# Base_Station_Schematic.net
KiCad netlist of a schematic drawn in Altium Designer
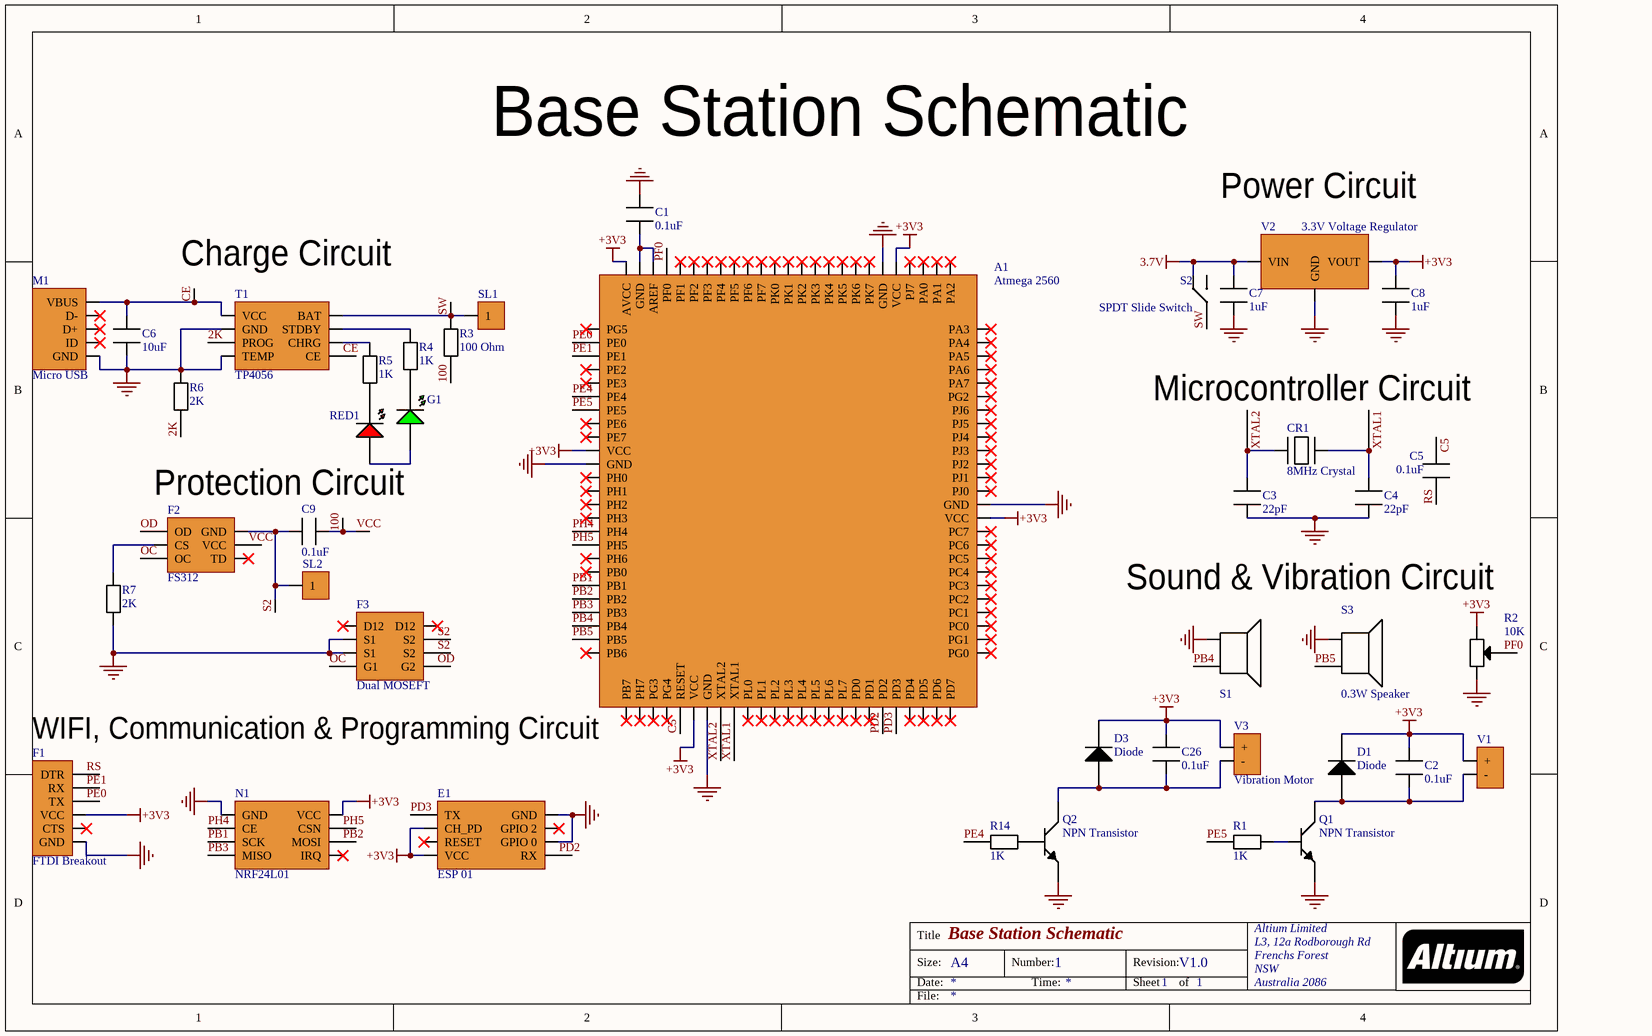
[diagram p0: Base Station Schematic.SchDoc]

(export (version "E")
  (design (tool "Eeschema 10.0.6"))
  (components
    (comp (ref "A1")
      (value "Atmega 2560")
      (footprint "Atmega 2560")
      (fields
        (field (name "MANUFACTURER") "Microchip / Atmel")
        (field (name "MANUFACTURER PART NUMBER") "ATMEGA2560V-8AU")
      )
      (libsource (lib "Schematic Library") (part "ATMEGA2560V-8AU"))
    )
    (comp (ref "C1")
      (value "0.1uF")
      (footprint "0.1uF Capacitor")
      (description "CAP CER 0.1UF 25V X7R 0603")
      (fields
        (field (name "MANUFACTURER") "Kyocera AVX")
        (field (name "MANUFACTURER PART NUMBER") "06033C104KAT4A")
      )
      (libsource (lib "Schematic Library") (part "06033C104KAT4A"))
    )
    (comp (ref "C2")
      (value "0.1uF")
      (footprint "0.1uF Capacitor")
      (description "CAP CER 0.1UF 25V X7R 0603")
      (fields
        (field (name "MANUFACTURER") "Kyocera AVX")
        (field (name "MANUFACTURER PART NUMBER") "06033C104KAT4A")
      )
      (libsource (lib "Schematic Library") (part "06033C104KAT4A"))
    )
    (comp (ref "C3")
      (value "22pF")
      (footprint "22pF Capacitor")
      (description "Cap Ceramic 22pF 50V C0G 5% SMD 0603 125C Paper T/R")
      (fields
        (field (name "MANUFACTURER") "Kyocera AVX")
        (field (name "MANUFACTURER PART NUMBER") "06035A220JAT2A")
      )
      (libsource (lib "Schematic Library") (part "06035A220JAT2A"))
    )
    (comp (ref "C4")
      (value "22pF")
      (footprint "22pF Capacitor")
      (description "Cap Ceramic 22pF 50V C0G 5% SMD 0603 125C Paper T/R")
      (fields
        (field (name "MANUFACTURER") "Kyocera AVX")
        (field (name "MANUFACTURER PART NUMBER") "06035A220JAT2A")
      )
      (libsource (lib "Schematic Library") (part "06035A220JAT2A"))
    )
    (comp (ref "C5")
      (value "0.1uF")
      (footprint "0.1uF Capacitor")
      (description "CAP CER 0.1UF 25V X7R 0603")
      (fields
        (field (name "MANUFACTURER") "Kyocera AVX")
        (field (name "MANUFACTURER PART NUMBER") "06033C104KAT4A")
      )
      (libsource (lib "Schematic Library") (part "06033C104KAT4A"))
    )
    (comp (ref "C6")
      (value "10uF")
      (footprint "10uF Capactior")
      (fields
        (field (name "MANUFACTURER") "Kyocera AVX")
        (field (name "MANUFACTURER PART NUMBER") "06036D106MAT2A")
        (field (name "TOLERANCE") "20%")
      )
      (libsource (lib "Schematic Library") (part "06036D106MAT2A"))
    )
    (comp (ref "C7")
      (value "1uF")
      (footprint "1uF Capacitor")
      (description "Cap Ceramic 1uF 10V X5R 10% Pad SMD 0603 85C T/R")
      (fields
        (field (name "MANUFACTURER") "Kyocera AVX")
        (field (name "MANUFACTURER PART NUMBER") "0603ZD105KAT2A")
      )
      (libsource (lib "Schematic Library") (part "0603ZD105KAT2A"))
    )
    (comp (ref "C8")
      (value "1uF")
      (footprint "1uF Capacitor")
      (description "Cap Ceramic 1uF 10V X5R 10% Pad SMD 0603 85C T/R")
      (fields
        (field (name "MANUFACTURER") "Kyocera AVX")
        (field (name "MANUFACTURER PART NUMBER") "0603ZD105KAT2A")
      )
      (libsource (lib "Schematic Library") (part "0603ZD105KAT2A"))
    )
    (comp (ref "C9")
      (value "0.1uF")
      (footprint "0.1uF Capacitor")
      (description "CAP CER 0.1UF 25V X7R 0603")
      (fields
        (field (name "MANUFACTURER") "Kyocera AVX")
        (field (name "MANUFACTURER PART NUMBER") "06033C104KAT4A")
      )
      (libsource (lib "Schematic Library") (part "06033C104KAT4A"))
    )
    (comp (ref "C26")
      (value "0.1uF")
      (footprint "0.1uF Capacitor")
      (description "CAP CER 0.1UF 25V X7R 0603")
      (fields
        (field (name "MANUFACTURER") "Kyocera AVX")
        (field (name "MANUFACTURER PART NUMBER") "06033C104KAT4A")
      )
      (libsource (lib "Schematic Library") (part "06033C104KAT4A"))
    )
    (comp (ref "CR1")
      (value "8MHz Crystal")
      (footprint "8MHz Crystal")
      (description "Crystal 8MHz ±30ppm (Tol) ±50ppm (Stability) 20pF FUND 80Ohm 2-Pin HC-49/SDLF SMD T/R")
      (fields
        (field (name "MANUFACTURER") "Fox Electronics")
        (field (name "MANUFACTURER PART NUMBER") "FC4SDCBMF8.0-T1")
      )
      (libsource (lib "Schematic Library") (part "FC4SDCBMF8.0-T1"))
    )
    (comp (ref "D1")
      (value "Diode")
      (footprint "Diode")
      (description "BOURNS - CD0603-B0240R - Kleinsignal-Schottky-Diode, Einfach, 40 V, 200 mA, 500 mV, 2 A, 125 °C")
      (fields
        (field (name "MANUFACTURER") "Bourns")
        (field (name "MANUFACTURER PART NUMBER") "CD0603-B0240R")
      )
      (libsource (lib "Schematic Library") (part "CD0603-B0240R"))
    )
    (comp (ref "D3")
      (value "Diode")
      (footprint "Diode")
      (description "BOURNS - CD0603-B0240R - Kleinsignal-Schottky-Diode, Einfach, 40 V, 200 mA, 500 mV, 2 A, 125 °C")
      (fields
        (field (name "MANUFACTURER") "Bourns")
        (field (name "MANUFACTURER PART NUMBER") "CD0603-B0240R")
      )
      (libsource (lib "Schematic Library") (part "CD0603-B0240R"))
    )
    (comp (ref "E1")
      (value "ESP 01")
      (footprint "ESP 01")
      (description "ESP8266 ESP-01 Serial WIFI Wireless Transceiver Module Send Receive LWIP AP+STA")
      (libsource (lib "Schematic Library") (part "ESP 01"))
    )
    (comp (ref "F1")
      (value "FTDI Breakout")
      (footprint "FTDI")
      (description "FTDI USB to TTL serial converter module")
      (libsource (lib "Schematic Library") (part "FTDI"))
    )
    (comp (ref "F2")
      (value "FS312")
      (footprint "FS312")
      (description "ONE CELL LI-ION/LI-PO BATTERY PROTECTION IC")
      (libsource (lib "Schematic Library") (part "FS312"))
    )
    (comp (ref "F3")
      (value "Dual MOSEFT")
      (footprint "FS8205")
      (description "FS8205A DUAL N-CHANNEL POWER MOSFET")
      (libsource (lib "Schematic Library") (part "FS8205"))
    )
    (comp (ref "G1")
      (value "Green LED")
      (footprint "Green LED")
      (description "WURTH ELEKTRONIK - 151051VS04000 - LED, Green, Through Hole, T-1 3/4 (5mm), 30 mA, 2.1 V, 572 nm")
      (fields
        (field (name "MANUFACTURER") "Wurth Electronics")
        (field (name "MANUFACTURER PART NUMBER") "151051VS04000")
      )
      (libsource (lib "Schematic Library") (part "151051VS04000"))
    )
    (comp (ref "M1")
      (value "Micro USB")
      (footprint "Micro USB")
      (fields
        (field (name "MANUFACTURER") "Wurth Electronics")
        (field (name "MANUFACTURER PART NUMBER") "629105136821")
      )
      (libsource (lib "Schematic Library") (part "629105136821"))
    )
    (comp (ref "N1")
      (value "NRF24L01")
      (footprint "NRF24L01")
      (description "3.3V NRF24L01 WIRELESS RF MODULE")
      (libsource (lib "Schematic Library") (part "NRF24L01"))
    )
    (comp (ref "Q1")
      (value "NPN Transistor")
      (footprint "NPN Transistor")
      (description "MMBT3904 Series 40 V 200 mA 250 mW NPN Switching Transistor - SOT-23-3")
      (fields
        (field (name "MANUFACTURER") "Nexperia")
        (field (name "MANUFACTURER PART NUMBER") "MMBT3904,215")
      )
      (libsource (lib "Schematic Library") (part "MMBT3904,215"))
    )
    (comp (ref "Q2")
      (value "NPN Transistor")
      (footprint "NPN Transistor")
      (description "MMBT3904 Series 40 V 200 mA 250 mW NPN Switching Transistor - SOT-23-3")
      (fields
        (field (name "MANUFACTURER") "Nexperia")
        (field (name "MANUFACTURER PART NUMBER") "MMBT3904,215")
      )
      (libsource (lib "Schematic Library") (part "MMBT3904,215"))
    )
    (comp (ref "R1")
      (value "1K")
      (footprint "1K Resistor")
      (description "RES 1K OHM 0.01% 1/10W 0603")
      (fields
        (field (name "MANUFACTURER") "Stackpole Electronics")
        (field (name "MANUFACTURER PART NUMBER") "RNCF0603TKY1K00")
      )
      (libsource (lib "Schematic Library") (part "RNCF0603TKY1K00"))
    )
    (comp (ref "R2")
      (value "10K")
      (footprint "10K Potentiometer")
      (fields
        (field (name "MANUFACTURER") "Bourns")
        (field (name "MANUFACTURER PART NUMBER") "91A1A-B28-B15L")
        (field (name "TOLERANCE") "20%")
      )
      (libsource (lib "Schematic Library") (part "91A1A-B28-B15L"))
    )
    (comp (ref "R3")
      (value "100 Ohm")
      (footprint "100 Ohm Resistor")
      (description "RES SMD 100 OHM 0.01% 1/10W 0603")
      (fields
        (field (name "MANUFACTURER") "Stackpole Electronics")
        (field (name "MANUFACTURER PART NUMBER") "RNCF0603TKY100R")
      )
      (libsource (lib "Schematic Library") (part "RNCF0603TKY100R"))
    )
    (comp (ref "R4")
      (value "1K")
      (footprint "1K Resistor")
      (description "RES 1K OHM 0.01% 1/10W 0603")
      (fields
        (field (name "MANUFACTURER") "Stackpole Electronics")
        (field (name "MANUFACTURER PART NUMBER") "RNCF0603TKY1K00")
      )
      (libsource (lib "Schematic Library") (part "RNCF0603TKY1K00"))
    )
    (comp (ref "R5")
      (value "1K")
      (footprint "1K Resistor")
      (description "RES 1K OHM 0.01% 1/10W 0603")
      (fields
        (field (name "MANUFACTURER") "Stackpole Electronics")
        (field (name "MANUFACTURER PART NUMBER") "RNCF0603TKY1K00")
      )
      (libsource (lib "Schematic Library") (part "RNCF0603TKY1K00"))
    )
    (comp (ref "R6")
      (value "2K")
      (footprint "2K Resistor")
      (description "RES 2K OHM 0.01% 1/10W 0603")
      (fields
        (field (name "MANUFACTURER") "Stackpole Electronics")
        (field (name "MANUFACTURER PART NUMBER") "RNCF0603TKY2K00")
      )
      (libsource (lib "Schematic Library") (part "RNCF0603TKY2K00"))
    )
    (comp (ref "R7")
      (value "2K")
      (footprint "2K Resistor")
      (description "RES 2K OHM 0.01% 1/10W 0603")
      (fields
        (field (name "MANUFACTURER") "Stackpole Electronics")
        (field (name "MANUFACTURER PART NUMBER") "RNCF0603TKY2K00")
      )
      (libsource (lib "Schematic Library") (part "RNCF0603TKY2K00"))
    )
    (comp (ref "R14")
      (value "1K")
      (footprint "1K Resistor")
      (description "RES 1K OHM 0.01% 1/10W 0603")
      (fields
        (field (name "MANUFACTURER") "Stackpole Electronics")
        (field (name "MANUFACTURER PART NUMBER") "RNCF0603TKY1K00")
      )
      (libsource (lib "Schematic Library") (part "RNCF0603TKY1K00"))
    )
    (comp (ref "RED1")
      (value "Red LED")
      (footprint "Red LED")
      (description "WURTH ELEKTRONIK - 151051RS11000 - LED, Red, Through Hole, T-1 3/4 (5mm), 30 mA, 2.1 V, 630 nm")
      (fields
        (field (name "MANUFACTURER") "Wurth Electronics")
        (field (name "MANUFACTURER PART NUMBER") "151051RS11000")
      )
      (libsource (lib "Schematic Library") (part "151051RS11000"))
    )
    (comp (ref "S1")
      (value "0.3W Speaker")
      (footprint "0.3W Speaker")
      (description "SPEAKER, 8OHM, 0.3W, 60MM")
      (fields
        (field (name "MANUFACTURER") "CQR Components")
        (field (name "MANUFACTURER PART NUMBER") "SPEAKERMINIATURE2.5\"8OHM")
      )
      (libsource (lib "Schematic Library") (part "SPEAKERMINIATURE2.5{dblquote}8OHM"))
    )
    (comp (ref "S2")
      (value "SPDT Slide Switch")
      (footprint "Slide Switch")
      (description "Slide Switch, JS Series, SPDT, Right Angle, SMD, 100 mA ;RoHS Compliant: Yes")
      (fields
        (field (name "MANUFACTURER") "ITT C&K")
        (field (name "MANUFACTURER PART NUMBER") "JS102011SAQN")
      )
      (libsource (lib "Schematic Library") (part "JS102011SAQN"))
    )
    (comp (ref "S3")
      (value "0.3W Speaker")
      (footprint "0.3W Speaker")
      (description "SPEAKER, 8OHM, 0.3W, 60MM")
      (fields
        (field (name "MANUFACTURER") "CQR Components")
        (field (name "MANUFACTURER PART NUMBER") "SPEAKERMINIATURE2.5\"8OHM")
      )
      (libsource (lib "Schematic Library") (part "SPEAKERMINIATURE2.5{dblquote}8OHM"))
    )
    (comp (ref "SL1")
      (value "Solder Pads")
      (footprint "Solder Pads")
      (description "CONN HEADER VERT 1POS")
      (fields
        (field (name "MANUFACTURER") "Wurth Electronics")
        (field (name "MANUFACTURER PART NUMBER") "61300111121")
      )
      (libsource (lib "Schematic Library") (part "61300111121"))
    )
    (comp (ref "SL2")
      (value "Solder Pads")
      (footprint "Solder Pads")
      (description "CONN HEADER VERT 1POS")
      (fields
        (field (name "MANUFACTURER") "Wurth Electronics")
        (field (name "MANUFACTURER PART NUMBER") "61300111121")
      )
      (libsource (lib "Schematic Library") (part "61300111121"))
    )
    (comp (ref "T1")
      (value "TP4056")
      (footprint "TP4056")
      (description "TP4056 1A Standalone Linear Li-lon Battery Charger with Thermal\r\nRegulation in SOP-8")
      (libsource (lib "Schematic Library") (part "TP4056"))
    )
    (comp (ref "V1")
      (value "Vibration Motor")
      (footprint "Vibration Motor")
      (description "Vibration Erm Motor 9000 Rpm 3V")
      (fields
        (field (name "MANUFACTURER") "Jinlong Machinery & Electronics")
        (field (name "MANUFACTURER PART NUMBER") "C1030B028F")
      )
      (libsource (lib "") (part "C1030B028F_1"))
    )
    (comp (ref "V2")
      (value "3.3V Voltage Regulator")
      (footprint "Voltage Regulator")
      (description "IC REG LINEAR 3.3V 1A SOT223")
      (fields
        (field (name "MANUFACTURER") "Diodes")
        (field (name "MANUFACTURER PART NUMBER") "AZ1117EH-3.3TRG1")
      )
      (libsource (lib "Schematic Library") (part "AZ1117EH-3.3TRG1"))
    )
    (comp (ref "V3")
      (value "Vibration Motor")
      (footprint "Vibration Motor")
      (description "Vibration Erm Motor 9000 Rpm 3V")
      (fields
        (field (name "MANUFACTURER") "Jinlong Machinery & Electronics")
        (field (name "MANUFACTURER PART NUMBER") "C1030B028F")
      )
      (libsource (lib "Schematic Library") (part "C1030B028F"))
    )
  )
  (nets
    (net (code "1") (name "+3V3") (class "Default")
      (node (ref "A1") (pin "10") (pinfunction "VCC_10") (pintype "passive"))
      (node (ref "A1") (pin "100") (pinfunction "AVCC_100") (pintype "passive"))
      (node (ref "A1") (pin "31") (pinfunction "VCC_31") (pintype "passive"))
      (node (ref "A1") (pin "61") (pinfunction "VCC_61") (pintype "passive"))
      (node (ref "A1") (pin "80") (pinfunction "VCC_80") (pintype "passive"))
      (node (ref "C2") (pin "1") (pinfunction "1_1") (pintype "passive"))
      (node (ref "C26") (pin "2") (pinfunction "2_2") (pintype "passive"))
      (node (ref "C8") (pin "2") (pinfunction "2_2") (pintype "passive"))
      (node (ref "D1") (pin "1") (pinfunction "1_1") (pintype "passive"))
      (node (ref "D3") (pin "1") (pinfunction "1_1") (pintype "passive"))
      (node (ref "E1") (pin "2") (pinfunction "CH_PD_2") (pintype "passive"))
      (node (ref "E1") (pin "4") (pinfunction "VCC_4") (pintype "passive"))
      (node (ref "F1") (pin "4") (pinfunction "VCC_4") (pintype "passive"))
      (node (ref "N1") (pin "5") (pinfunction "VCC_5") (pintype "passive"))
      (node (ref "R2") (pin "1") (pinfunction "1_1") (pintype "passive"))
      (node (ref "V1") (pin "2") (pinfunction "+_2") (pintype "passive"))
      (node (ref "V2") (pin "2") (pinfunction "VOUT_2") (pintype "passive"))
      (node (ref "V3") (pin "2") (pinfunction "+_2") (pintype "passive"))
    )
    (net (code "2") (name "/2K") (class "Default")
      (node (ref "R6") (pin "1") (pinfunction "1_1") (pintype "passive"))
      (node (ref "T1") (pin "2") (pinfunction "PROG_2") (pintype "passive"))
    )
    (net (code "3") (name "/100") (class "Default")
      (node (ref "C9") (pin "1") (pinfunction "1_1") (pintype "passive"))
      (node (ref "F2") (pin "5") (pinfunction "VCC_5") (pintype "passive"))
      (node (ref "R3") (pin "2") (pinfunction "2_2") (pintype "passive"))
    )
    (net (code "4") (name "/C5") (class "Default")
      (node (ref "A1") (pin "30") (pinfunction "RESET_30") (pintype "passive"))
      (node (ref "C5") (pin "2") (pinfunction "2_2") (pintype "passive"))
    )
    (net (code "5") (name "/CE") (class "Default")
      (node (ref "C6") (pin "2") (pinfunction "2_2") (pintype "passive"))
      (node (ref "M1") (pin "1") (pinfunction "VBUS_1") (pintype "passive"))
      (node (ref "T1") (pin "4") (pinfunction "VCC_4") (pintype "passive"))
      (node (ref "T1") (pin "8") (pinfunction "CE_8") (pintype "passive"))
    )
    (net (code "6") (name "/OC") (class "Default")
      (node (ref "F2") (pin "3") (pinfunction "OC_3") (pintype "passive"))
      (node (ref "F3") (pin "4") (pinfunction "G1_4") (pintype "passive"))
    )
    (net (code "7") (name "/OD") (class "Default")
      (node (ref "F2") (pin "1") (pinfunction "OD_1") (pintype "passive"))
      (node (ref "F3") (pin "5") (pinfunction "G2_5") (pintype "passive"))
    )
    (net (code "8") (name "/PB1") (class "Default")
      (node (ref "A1") (pin "20") (pinfunction "PB1_20") (pintype "passive"))
      (node (ref "N1") (pin "3") (pinfunction "SCK_3") (pintype "passive"))
    )
    (net (code "9") (name "/PB2") (class "Default")
      (node (ref "A1") (pin "21") (pinfunction "PB2_21") (pintype "passive"))
      (node (ref "N1") (pin "7") (pinfunction "MOSI_7") (pintype "passive"))
    )
    (net (code "10") (name "/PB3") (class "Default")
      (node (ref "A1") (pin "22") (pinfunction "PB3_22") (pintype "passive"))
      (node (ref "N1") (pin "4") (pinfunction "MISO_4") (pintype "passive"))
    )
    (net (code "11") (name "/PB4") (class "Default")
      (node (ref "A1") (pin "23") (pinfunction "PB4_23") (pintype "passive"))
      (node (ref "S1") (pin "2") (pinfunction "2_2") (pintype "passive"))
    )
    (net (code "12") (name "/PB5") (class "Default")
      (node (ref "A1") (pin "24") (pinfunction "PB5_24") (pintype "passive"))
      (node (ref "S3") (pin "2") (pinfunction "2_2") (pintype "passive"))
    )
    (net (code "13") (name "/PD2") (class "Default")
      (node (ref "A1") (pin "45") (pinfunction "PD2_45") (pintype "passive"))
      (node (ref "E1") (pin "8") (pinfunction "RX_8") (pintype "passive"))
    )
    (net (code "14") (name "/PD3") (class "Default")
      (node (ref "A1") (pin "46") (pinfunction "PD3_46") (pintype "passive"))
      (node (ref "E1") (pin "1") (pinfunction "TX_1") (pintype "passive"))
    )
    (net (code "15") (name "/PE0") (class "Default")
      (node (ref "A1") (pin "2") (pinfunction "PE0_2") (pintype "passive"))
      (node (ref "F1") (pin "3") (pinfunction "TX_3") (pintype "passive"))
    )
    (net (code "16") (name "/PE1") (class "Default")
      (node (ref "A1") (pin "3") (pinfunction "PE1_3") (pintype "passive"))
      (node (ref "F1") (pin "2") (pinfunction "RX_2") (pintype "passive"))
    )
    (net (code "17") (name "/PE4") (class "Default")
      (node (ref "A1") (pin "6") (pinfunction "PE4_6") (pintype "passive"))
      (node (ref "R14") (pin "1") (pinfunction "1_1") (pintype "passive"))
    )
    (net (code "18") (name "/PE5") (class "Default")
      (node (ref "A1") (pin "7") (pinfunction "PE5_7") (pintype "passive"))
      (node (ref "R1") (pin "1") (pinfunction "1_1") (pintype "passive"))
    )
    (net (code "19") (name "/PF0") (class "Default")
      (node (ref "A1") (pin "97") (pinfunction "PF0_97") (pintype "passive"))
      (node (ref "R2") (pin "2") (pinfunction "2_2") (pintype "passive"))
    )
    (net (code "20") (name "/PH4") (class "Default")
      (node (ref "A1") (pin "16") (pinfunction "PH4_16") (pintype "passive"))
      (node (ref "N1") (pin "2") (pinfunction "CE_2") (pintype "passive"))
    )
    (net (code "21") (name "/PH5") (class "Default")
      (node (ref "A1") (pin "17") (pinfunction "PH5_17") (pintype "passive"))
      (node (ref "N1") (pin "6") (pinfunction "CSN_6") (pintype "passive"))
    )
    (net (code "22") (name "/RS") (class "Default")
      (node (ref "C5") (pin "1") (pinfunction "1_1") (pintype "passive"))
      (node (ref "F1") (pin "1") (pinfunction "DTR_1") (pintype "passive"))
    )
    (net (code "23") (name "/S2") (class "Default")
      (node (ref "C9") (pin "2") (pinfunction "2_2") (pintype "passive"))
      (node (ref "F2") (pin "6") (pinfunction "GND_6") (pintype "passive"))
      (node (ref "F3") (pin "6") (pinfunction "S2_6") (pintype "passive"))
      (node (ref "F3") (pin "7") (pinfunction "S2_7") (pintype "passive"))
      (node (ref "SL2") (pin "1") (pinfunction "1_1") (pintype "passive"))
    )
    (net (code "24") (name "/SW") (class "Default")
      (node (ref "R3") (pin "1") (pinfunction "1_1") (pintype "passive"))
      (node (ref "S2") (pin "2") (pinfunction "2_2") (pintype "passive"))
      (node (ref "SL1") (pin "1") (pinfunction "1_1") (pintype "passive"))
      (node (ref "T1") (pin "5") (pinfunction "BAT_5") (pintype "passive"))
    )
    (net (code "25") (name "/XTAL1") (class "Default")
      (node (ref "A1") (pin "34") (pinfunction "XTAL1_34") (pintype "passive"))
      (node (ref "C4") (pin "2") (pinfunction "2_2") (pintype "passive"))
      (node (ref "CR1") (pin "2") (pinfunction "2_2") (pintype "passive"))
    )
    (net (code "26") (name "/XTAL2") (class "Default")
      (node (ref "A1") (pin "33") (pinfunction "XTAL2_33") (pintype "passive"))
      (node (ref "C3") (pin "2") (pinfunction "2_2") (pintype "passive"))
      (node (ref "CR1") (pin "1") (pinfunction "1_1") (pintype "passive"))
    )
    (net (code "27") (name "3.7V") (class "Default")
      (node (ref "C7") (pin "2") (pinfunction "2_2") (pintype "passive"))
      (node (ref "S2") (pin "3") (pinfunction "3_3") (pintype "passive"))
      (node (ref "V2") (pin "3") (pinfunction "VIN_3") (pintype "passive"))
    )
    (net (code "28") (name "GND") (class "Default")
      (node (ref "A1") (pin "11") (pinfunction "GND_11") (pintype "passive"))
      (node (ref "A1") (pin "32") (pinfunction "GND_32") (pintype "passive"))
      (node (ref "A1") (pin "62") (pinfunction "GND_62") (pintype "passive"))
      (node (ref "A1") (pin "81") (pinfunction "GND_81") (pintype "passive"))
      (node (ref "C1") (pin "1") (pinfunction "1_1") (pintype "passive"))
      (node (ref "C3") (pin "1") (pinfunction "1_1") (pintype "passive"))
      (node (ref "C4") (pin "1") (pinfunction "1_1") (pintype "passive"))
      (node (ref "C6") (pin "1") (pinfunction "1_1") (pintype "passive"))
      (node (ref "C7") (pin "1") (pinfunction "1_1") (pintype "passive"))
      (node (ref "C8") (pin "1") (pinfunction "1_1") (pintype "passive"))
      (node (ref "E1") (pin "5") (pinfunction "GND_5") (pintype "passive"))
      (node (ref "E1") (pin "7") (pinfunction "GPIO_0_7") (pintype "passive"))
      (node (ref "F1") (pin "6") (pinfunction "GND_6") (pintype "passive"))
      (node (ref "F3") (pin "2") (pinfunction "S1_2") (pintype "passive"))
      (node (ref "F3") (pin "3") (pinfunction "S1_3") (pintype "passive"))
      (node (ref "M1") (pin "5") (pinfunction "GND_5") (pintype "passive"))
      (node (ref "N1") (pin "1") (pinfunction "GND_1") (pintype "passive"))
      (node (ref "Q1") (pin "2") (pinfunction "2_2") (pintype "passive"))
      (node (ref "Q2") (pin "2") (pinfunction "2_2") (pintype "passive"))
      (node (ref "R2") (pin "3") (pinfunction "3_3") (pintype "passive"))
      (node (ref "R6") (pin "2") (pinfunction "2_2") (pintype "passive"))
      (node (ref "R7") (pin "1") (pinfunction "1_1") (pintype "passive"))
      (node (ref "S1") (pin "1") (pinfunction "1_1") (pintype "passive"))
      (node (ref "S3") (pin "1") (pinfunction "1_1") (pintype "passive"))
      (node (ref "T1") (pin "1") (pinfunction "TEMP_1") (pintype "passive"))
      (node (ref "T1") (pin "3") (pinfunction "GND_3") (pintype "passive"))
      (node (ref "V2") (pin "1") (pinfunction "GND_1") (pintype "passive"))
    )
    (net (code "29") (name "Net-(A1-AREF)") (class "Default")
      (node (ref "A1") (pin "98") (pinfunction "AREF_98") (pintype "passive"))
      (node (ref "A1") (pin "99") (pinfunction "GND_99") (pintype "passive"))
      (node (ref "C1") (pin "2") (pinfunction "2_2") (pintype "passive"))
    )
    (net (code "30") (name "Net-(F2-CS)") (class "Default")
      (node (ref "F2") (pin "2") (pinfunction "CS_2") (pintype "passive"))
      (node (ref "R7") (pin "2") (pinfunction "2_2") (pintype "passive"))
    )
    (net (code "31") (name "Net-(G1-Pad1)") (class "Default")
      (node (ref "G1") (pin "1") (pinfunction "1_1") (pintype "passive"))
      (node (ref "R4") (pin "1") (pinfunction "1_1") (pintype "passive"))
    )
    (net (code "32") (name "Net-(G1-Pad2)") (class "Default")
      (node (ref "G1") (pin "2") (pinfunction "2_2") (pintype "passive"))
      (node (ref "RED1") (pin "2") (pinfunction "2_2") (pintype "passive"))
    )
    (net (code "33") (name "Net-(Q1-Pad1)") (class "Default")
      (node (ref "Q1") (pin "1") (pinfunction "1_1") (pintype "passive"))
      (node (ref "R1") (pin "2") (pinfunction "2_2") (pintype "passive"))
    )
    (net (code "34") (name "Net-(Q2-Pad1)") (class "Default")
      (node (ref "Q2") (pin "1") (pinfunction "1_1") (pintype "passive"))
      (node (ref "R14") (pin "2") (pinfunction "2_2") (pintype "passive"))
    )
    (net (code "35") (name "Net-(R5-Pad1)") (class "Default")
      (node (ref "R5") (pin "1") (pinfunction "1_1") (pintype "passive"))
      (node (ref "RED1") (pin "1") (pinfunction "1_1") (pintype "passive"))
    )
    (net (code "36") (name "Net-(T1-CHRG)") (class "Default")
      (node (ref "R5") (pin "2") (pinfunction "2_2") (pintype "passive"))
      (node (ref "T1") (pin "7") (pinfunction "CHRG_7") (pintype "passive"))
    )
    (net (code "37") (name "Net-(T1-STDBY)") (class "Default")
      (node (ref "R4") (pin "2") (pinfunction "2_2") (pintype "passive"))
      (node (ref "T1") (pin "6") (pinfunction "STDBY_6") (pintype "passive"))
    )
    (net (code "38") (name "Net-(V1--)") (class "Default")
      (node (ref "C2") (pin "2") (pinfunction "2_2") (pintype "passive"))
      (node (ref "D1") (pin "2") (pinfunction "2_2") (pintype "passive"))
      (node (ref "Q1") (pin "3") (pinfunction "3_3") (pintype "passive"))
      (node (ref "V1") (pin "1") (pinfunction "-_1") (pintype "passive"))
    )
    (net (code "39") (name "Net-(V3--)") (class "Default")
      (node (ref "C26") (pin "1") (pinfunction "1_1") (pintype "passive"))
      (node (ref "D3") (pin "2") (pinfunction "2_2") (pintype "passive"))
      (node (ref "Q2") (pin "3") (pinfunction "3_3") (pintype "passive"))
      (node (ref "V3") (pin "1") (pinfunction "-_1") (pintype "passive"))
    )
    (net (code "40") (name "unconnected-(A1-PA0-Pad78)") (class "Default")
      (node (ref "A1") (pin "78") (pinfunction "PA0_78") (pintype "passive+no_connect"))
    )
    (net (code "41") (name "unconnected-(A1-PA1-Pad77)") (class "Default")
      (node (ref "A1") (pin "77") (pinfunction "PA1_77") (pintype "passive+no_connect"))
    )
    (net (code "42") (name "unconnected-(A1-PA2-Pad76)") (class "Default")
      (node (ref "A1") (pin "76") (pinfunction "PA2_76") (pintype "passive+no_connect"))
    )
    (net (code "43") (name "unconnected-(A1-PA3-Pad75)") (class "Default")
      (node (ref "A1") (pin "75") (pinfunction "PA3_75") (pintype "passive+no_connect"))
    )
    (net (code "44") (name "unconnected-(A1-PA4-Pad74)") (class "Default")
      (node (ref "A1") (pin "74") (pinfunction "PA4_74") (pintype "passive+no_connect"))
    )
    (net (code "45") (name "unconnected-(A1-PA5-Pad73)") (class "Default")
      (node (ref "A1") (pin "73") (pinfunction "PA5_73") (pintype "passive+no_connect"))
    )
    (net (code "46") (name "unconnected-(A1-PA6-Pad72)") (class "Default")
      (node (ref "A1") (pin "72") (pinfunction "PA6_72") (pintype "passive+no_connect"))
    )
    (net (code "47") (name "unconnected-(A1-PA7-Pad71)") (class "Default")
      (node (ref "A1") (pin "71") (pinfunction "PA7_71") (pintype "passive+no_connect"))
    )
    (net (code "48") (name "unconnected-(A1-PB0-Pad19)") (class "Default")
      (node (ref "A1") (pin "19") (pinfunction "PB0_19") (pintype "passive+no_connect"))
    )
    (net (code "49") (name "unconnected-(A1-PB6-Pad25)") (class "Default")
      (node (ref "A1") (pin "25") (pinfunction "PB6_25") (pintype "passive+no_connect"))
    )
    (net (code "50") (name "unconnected-(A1-PB7-Pad26)") (class "Default")
      (node (ref "A1") (pin "26") (pinfunction "PB7_26") (pintype "passive+no_connect"))
    )
    (net (code "51") (name "unconnected-(A1-PC0-Pad53)") (class "Default")
      (node (ref "A1") (pin "53") (pinfunction "PC0_53") (pintype "passive+no_connect"))
    )
    (net (code "52") (name "unconnected-(A1-PC1-Pad54)") (class "Default")
      (node (ref "A1") (pin "54") (pinfunction "PC1_54") (pintype "passive+no_connect"))
    )
    (net (code "53") (name "unconnected-(A1-PC2-Pad55)") (class "Default")
      (node (ref "A1") (pin "55") (pinfunction "PC2_55") (pintype "passive+no_connect"))
    )
    (net (code "54") (name "unconnected-(A1-PC3-Pad56)") (class "Default")
      (node (ref "A1") (pin "56") (pinfunction "PC3_56") (pintype "passive+no_connect"))
    )
    (net (code "55") (name "unconnected-(A1-PC4-Pad57)") (class "Default")
      (node (ref "A1") (pin "57") (pinfunction "PC4_57") (pintype "passive+no_connect"))
    )
    (net (code "56") (name "unconnected-(A1-PC5-Pad58)") (class "Default")
      (node (ref "A1") (pin "58") (pinfunction "PC5_58") (pintype "passive+no_connect"))
    )
    (net (code "57") (name "unconnected-(A1-PC6-Pad59)") (class "Default")
      (node (ref "A1") (pin "59") (pinfunction "PC6_59") (pintype "passive+no_connect"))
    )
    (net (code "58") (name "unconnected-(A1-PC7-Pad60)") (class "Default")
      (node (ref "A1") (pin "60") (pinfunction "PC7_60") (pintype "passive+no_connect"))
    )
    (net (code "59") (name "unconnected-(A1-PD0-Pad43)") (class "Default")
      (node (ref "A1") (pin "43") (pinfunction "PD0_43") (pintype "passive+no_connect"))
    )
    (net (code "60") (name "unconnected-(A1-PD1-Pad44)") (class "Default")
      (node (ref "A1") (pin "44") (pinfunction "PD1_44") (pintype "passive+no_connect"))
    )
    (net (code "61") (name "unconnected-(A1-PD4-Pad47)") (class "Default")
      (node (ref "A1") (pin "47") (pinfunction "PD4_47") (pintype "passive+no_connect"))
    )
    (net (code "62") (name "unconnected-(A1-PD5-Pad48)") (class "Default")
      (node (ref "A1") (pin "48") (pinfunction "PD5_48") (pintype "passive+no_connect"))
    )
    (net (code "63") (name "unconnected-(A1-PD6-Pad49)") (class "Default")
      (node (ref "A1") (pin "49") (pinfunction "PD6_49") (pintype "passive+no_connect"))
    )
    (net (code "64") (name "unconnected-(A1-PD7-Pad50)") (class "Default")
      (node (ref "A1") (pin "50") (pinfunction "PD7_50") (pintype "passive+no_connect"))
    )
    (net (code "65") (name "unconnected-(A1-PE2-Pad4)") (class "Default")
      (node (ref "A1") (pin "4") (pinfunction "PE2_4") (pintype "passive+no_connect"))
    )
    (net (code "66") (name "unconnected-(A1-PE3-Pad5)") (class "Default")
      (node (ref "A1") (pin "5") (pinfunction "PE3_5") (pintype "passive+no_connect"))
    )
    (net (code "67") (name "unconnected-(A1-PE6-Pad8)") (class "Default")
      (node (ref "A1") (pin "8") (pinfunction "PE6_8") (pintype "passive+no_connect"))
    )
    (net (code "68") (name "unconnected-(A1-PE7-Pad9)") (class "Default")
      (node (ref "A1") (pin "9") (pinfunction "PE7_9") (pintype "passive+no_connect"))
    )
    (net (code "69") (name "unconnected-(A1-PF1-Pad96)") (class "Default")
      (node (ref "A1") (pin "96") (pinfunction "PF1_96") (pintype "passive+no_connect"))
    )
    (net (code "70") (name "unconnected-(A1-PF2-Pad95)") (class "Default")
      (node (ref "A1") (pin "95") (pinfunction "PF2_95") (pintype "passive+no_connect"))
    )
    (net (code "71") (name "unconnected-(A1-PF3-Pad94)") (class "Default")
      (node (ref "A1") (pin "94") (pinfunction "PF3_94") (pintype "passive+no_connect"))
    )
    (net (code "72") (name "unconnected-(A1-PF4-Pad93)") (class "Default")
      (node (ref "A1") (pin "93") (pinfunction "PF4_93") (pintype "passive+no_connect"))
    )
    (net (code "73") (name "unconnected-(A1-PF5-Pad92)") (class "Default")
      (node (ref "A1") (pin "92") (pinfunction "PF5_92") (pintype "passive+no_connect"))
    )
    (net (code "74") (name "unconnected-(A1-PF6-Pad91)") (class "Default")
      (node (ref "A1") (pin "91") (pinfunction "PF6_91") (pintype "passive+no_connect"))
    )
    (net (code "75") (name "unconnected-(A1-PF7-Pad90)") (class "Default")
      (node (ref "A1") (pin "90") (pinfunction "PF7_90") (pintype "passive+no_connect"))
    )
    (net (code "76") (name "unconnected-(A1-PG0-Pad51)") (class "Default")
      (node (ref "A1") (pin "51") (pinfunction "PG0_51") (pintype "passive+no_connect"))
    )
    (net (code "77") (name "unconnected-(A1-PG1-Pad52)") (class "Default")
      (node (ref "A1") (pin "52") (pinfunction "PG1_52") (pintype "passive+no_connect"))
    )
    (net (code "78") (name "unconnected-(A1-PG2-Pad70)") (class "Default")
      (node (ref "A1") (pin "70") (pinfunction "PG2_70") (pintype "passive+no_connect"))
    )
    (net (code "79") (name "unconnected-(A1-PG3-Pad28)") (class "Default")
      (node (ref "A1") (pin "28") (pinfunction "PG3_28") (pintype "passive+no_connect"))
    )
    (net (code "80") (name "unconnected-(A1-PG4-Pad29)") (class "Default")
      (node (ref "A1") (pin "29") (pinfunction "PG4_29") (pintype "passive+no_connect"))
    )
    (net (code "81") (name "unconnected-(A1-PG5-Pad1)") (class "Default")
      (node (ref "A1") (pin "1") (pinfunction "PG5_1") (pintype "passive+no_connect"))
    )
    (net (code "82") (name "unconnected-(A1-PH0-Pad12)") (class "Default")
      (node (ref "A1") (pin "12") (pinfunction "PH0_12") (pintype "passive+no_connect"))
    )
    (net (code "83") (name "unconnected-(A1-PH1-Pad13)") (class "Default")
      (node (ref "A1") (pin "13") (pinfunction "PH1_13") (pintype "passive+no_connect"))
    )
    (net (code "84") (name "unconnected-(A1-PH2-Pad14)") (class "Default")
      (node (ref "A1") (pin "14") (pinfunction "PH2_14") (pintype "passive+no_connect"))
    )
    (net (code "85") (name "unconnected-(A1-PH3-Pad15)") (class "Default")
      (node (ref "A1") (pin "15") (pinfunction "PH3_15") (pintype "passive+no_connect"))
    )
    (net (code "86") (name "unconnected-(A1-PH6-Pad18)") (class "Default")
      (node (ref "A1") (pin "18") (pinfunction "PH6_18") (pintype "passive+no_connect"))
    )
    (net (code "87") (name "unconnected-(A1-PH7-Pad27)") (class "Default")
      (node (ref "A1") (pin "27") (pinfunction "PH7_27") (pintype "passive+no_connect"))
    )
    (net (code "88") (name "unconnected-(A1-PJ0-Pad63)") (class "Default")
      (node (ref "A1") (pin "63") (pinfunction "PJ0_63") (pintype "passive+no_connect"))
    )
    (net (code "89") (name "unconnected-(A1-PJ1-Pad64)") (class "Default")
      (node (ref "A1") (pin "64") (pinfunction "PJ1_64") (pintype "passive+no_connect"))
    )
    (net (code "90") (name "unconnected-(A1-PJ2-Pad65)") (class "Default")
      (node (ref "A1") (pin "65") (pinfunction "PJ2_65") (pintype "passive+no_connect"))
    )
    (net (code "91") (name "unconnected-(A1-PJ3-Pad66)") (class "Default")
      (node (ref "A1") (pin "66") (pinfunction "PJ3_66") (pintype "passive+no_connect"))
    )
    (net (code "92") (name "unconnected-(A1-PJ4-Pad67)") (class "Default")
      (node (ref "A1") (pin "67") (pinfunction "PJ4_67") (pintype "passive+no_connect"))
    )
    (net (code "93") (name "unconnected-(A1-PJ5-Pad68)") (class "Default")
      (node (ref "A1") (pin "68") (pinfunction "PJ5_68") (pintype "passive+no_connect"))
    )
    (net (code "94") (name "unconnected-(A1-PJ6-Pad69)") (class "Default")
      (node (ref "A1") (pin "69") (pinfunction "PJ6_69") (pintype "passive+no_connect"))
    )
    (net (code "95") (name "unconnected-(A1-PJ7-Pad79)") (class "Default")
      (node (ref "A1") (pin "79") (pinfunction "PJ7_79") (pintype "passive+no_connect"))
    )
    (net (code "96") (name "unconnected-(A1-PK0-Pad89)") (class "Default")
      (node (ref "A1") (pin "89") (pinfunction "PK0_89") (pintype "passive+no_connect"))
    )
    (net (code "97") (name "unconnected-(A1-PK1-Pad88)") (class "Default")
      (node (ref "A1") (pin "88") (pinfunction "PK1_88") (pintype "passive+no_connect"))
    )
    (net (code "98") (name "unconnected-(A1-PK2-Pad87)") (class "Default")
      (node (ref "A1") (pin "87") (pinfunction "PK2_87") (pintype "passive+no_connect"))
    )
    (net (code "99") (name "unconnected-(A1-PK3-Pad86)") (class "Default")
      (node (ref "A1") (pin "86") (pinfunction "PK3_86") (pintype "passive+no_connect"))
    )
    (net (code "100") (name "unconnected-(A1-PK4-Pad85)") (class "Default")
      (node (ref "A1") (pin "85") (pinfunction "PK4_85") (pintype "passive+no_connect"))
    )
    (net (code "101") (name "unconnected-(A1-PK5-Pad84)") (class "Default")
      (node (ref "A1") (pin "84") (pinfunction "PK5_84") (pintype "passive+no_connect"))
    )
    (net (code "102") (name "unconnected-(A1-PK6-Pad83)") (class "Default")
      (node (ref "A1") (pin "83") (pinfunction "PK6_83") (pintype "passive+no_connect"))
    )
    (net (code "103") (name "unconnected-(A1-PK7-Pad82)") (class "Default")
      (node (ref "A1") (pin "82") (pinfunction "PK7_82") (pintype "passive+no_connect"))
    )
    (net (code "104") (name "unconnected-(A1-PL0-Pad35)") (class "Default")
      (node (ref "A1") (pin "35") (pinfunction "PL0_35") (pintype "passive+no_connect"))
    )
    (net (code "105") (name "unconnected-(A1-PL1-Pad36)") (class "Default")
      (node (ref "A1") (pin "36") (pinfunction "PL1_36") (pintype "passive+no_connect"))
    )
    (net (code "106") (name "unconnected-(A1-PL2-Pad37)") (class "Default")
      (node (ref "A1") (pin "37") (pinfunction "PL2_37") (pintype "passive+no_connect"))
    )
    (net (code "107") (name "unconnected-(A1-PL3-Pad38)") (class "Default")
      (node (ref "A1") (pin "38") (pinfunction "PL3_38") (pintype "passive+no_connect"))
    )
    (net (code "108") (name "unconnected-(A1-PL4-Pad39)") (class "Default")
      (node (ref "A1") (pin "39") (pinfunction "PL4_39") (pintype "passive+no_connect"))
    )
    (net (code "109") (name "unconnected-(A1-PL5-Pad40)") (class "Default")
      (node (ref "A1") (pin "40") (pinfunction "PL5_40") (pintype "passive+no_connect"))
    )
    (net (code "110") (name "unconnected-(A1-PL6-Pad41)") (class "Default")
      (node (ref "A1") (pin "41") (pinfunction "PL6_41") (pintype "passive+no_connect"))
    )
    (net (code "111") (name "unconnected-(A1-PL7-Pad42)") (class "Default")
      (node (ref "A1") (pin "42") (pinfunction "PL7_42") (pintype "passive+no_connect"))
    )
    (net (code "112") (name "unconnected-(E1-GPIO_2-Pad6)") (class "Default")
      (node (ref "E1") (pin "6") (pinfunction "GPIO_2_6") (pintype "passive+no_connect"))
    )
    (net (code "113") (name "unconnected-(E1-RESET-Pad3)") (class "Default")
      (node (ref "E1") (pin "3") (pinfunction "RESET_3") (pintype "passive+no_connect"))
    )
    (net (code "114") (name "unconnected-(F1-CTS-Pad5)") (class "Default")
      (node (ref "F1") (pin "5") (pinfunction "CTS_5") (pintype "passive+no_connect"))
    )
    (net (code "115") (name "unconnected-(F2-TD-Pad4)") (class "Default")
      (node (ref "F2") (pin "4") (pinfunction "TD_4") (pintype "passive+no_connect"))
    )
    (net (code "116") (name "unconnected-(F3-D12-Pad1)") (class "Default")
      (node (ref "F3") (pin "1") (pinfunction "D12_1") (pintype "passive+no_connect"))
    )
    (net (code "117") (name "unconnected-(F3-D12-Pad8)") (class "Default")
      (node (ref "F3") (pin "8") (pinfunction "D12_8") (pintype "passive+no_connect"))
    )
    (net (code "118") (name "unconnected-(M1-D+-Pad3)") (class "Default")
      (node (ref "M1") (pin "3") (pinfunction "D+_3") (pintype "passive+no_connect"))
    )
    (net (code "119") (name "unconnected-(M1-D--Pad2)") (class "Default")
      (node (ref "M1") (pin "2") (pinfunction "D-_2") (pintype "passive+no_connect"))
    )
    (net (code "120") (name "unconnected-(M1-ID-Pad4)") (class "Default")
      (node (ref "M1") (pin "4") (pinfunction "ID_4") (pintype "passive+no_connect"))
    )
    (net (code "121") (name "unconnected-(N1-IRQ-Pad8)") (class "Default")
      (node (ref "N1") (pin "8") (pinfunction "IRQ_8") (pintype "passive+no_connect"))
    )
    (net (code "122") (name "unconnected-(S2-Pad1)") (class "Default")
      (node (ref "S2") (pin "1") (pinfunction "1_1") (pintype "passive"))
    )
  )
)
